# My_STM32_BOARD_FUNCTION_SCH.net
KiCad netlist of a schematic drawn in Altium Designer
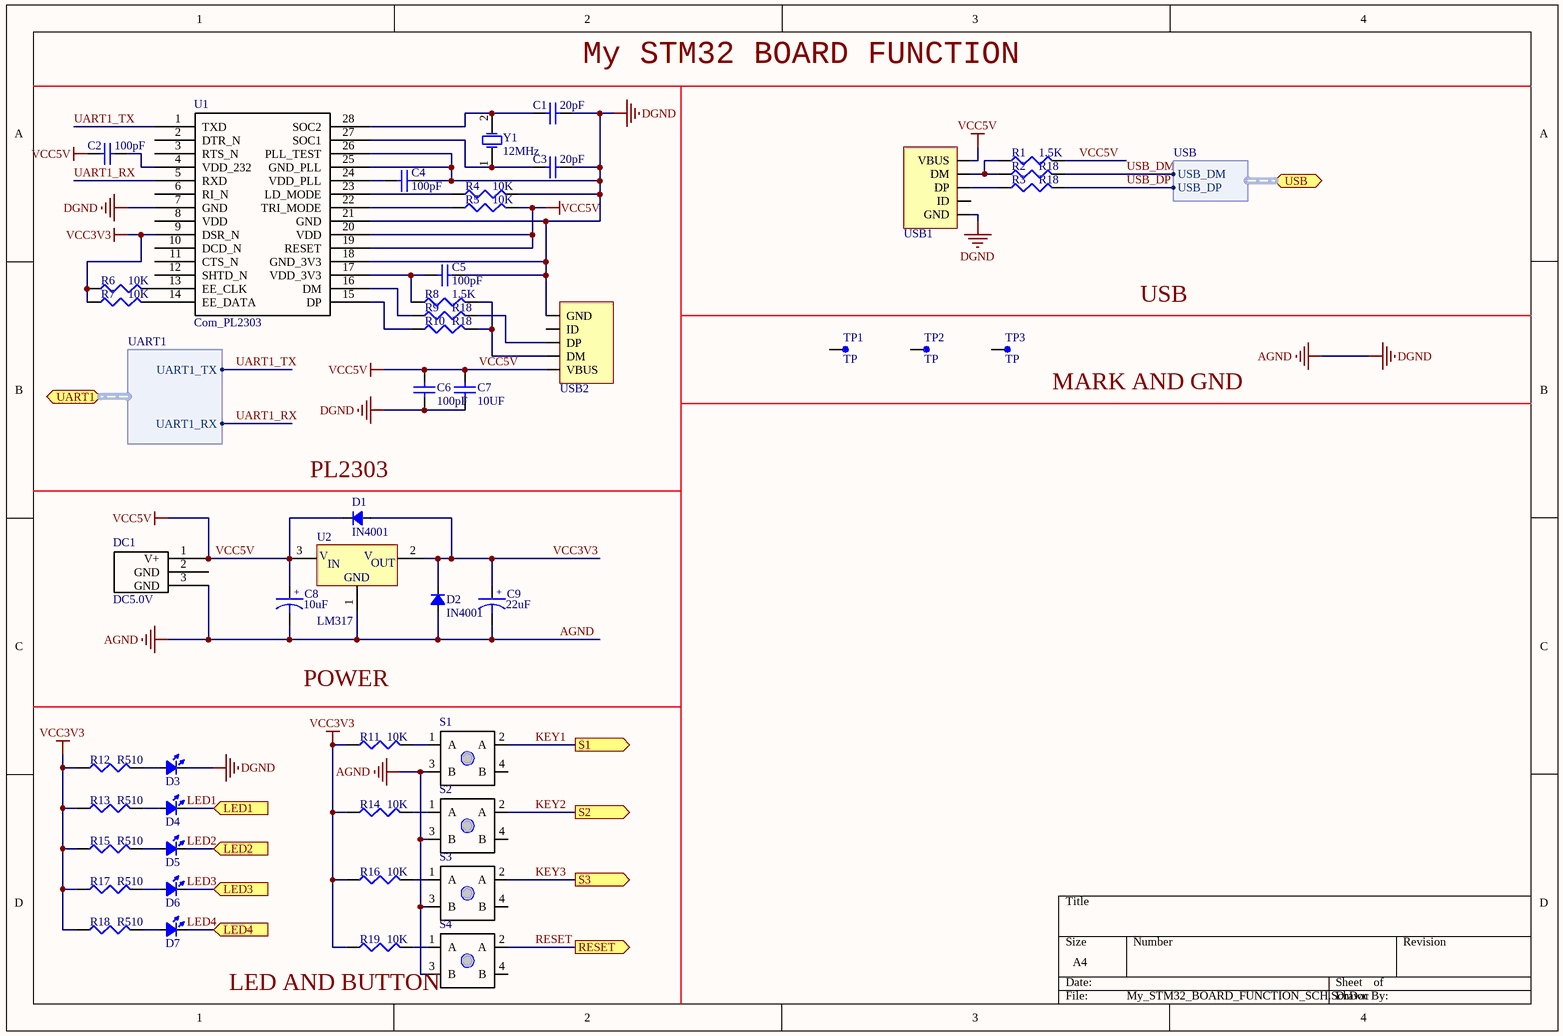
[diagram p0: My_STM32_BOARD_FUNCTION_SCH.SchDoc]

(export (version "E")
  (design (tool "Eeschema 10.0.6"))
  (components
    (comp (ref "C1")
      (value "20pF")
      (footprint "0402")
      (description "Capacitor")
      (fields (field (name "Comment") "Cap") (field (name "PUBLISHER") "Altium Limited"))
      (libsource (lib "Miscellaneous Devices") (part "Cap"))
    )
    (comp (ref "C2")
      (value "100pF")
      (footprint "0402")
      (description "Capacitor")
      (fields (field (name "Comment") "Cap") (field (name "PUBLISHER") "Altium Limited"))
      (libsource (lib "Miscellaneous Devices") (part "Cap"))
    )
    (comp (ref "C3")
      (value "20pF")
      (footprint "0402")
      (description "Capacitor")
      (fields (field (name "Comment") "Cap") (field (name "PUBLISHER") "Altium Limited"))
      (libsource (lib "Miscellaneous Devices") (part "Cap"))
    )
    (comp (ref "C4")
      (value "100pF")
      (footprint "0402")
      (description "Capacitor")
      (fields (field (name "Comment") "Cap") (field (name "PUBLISHER") "Altium Limited"))
      (libsource (lib "Miscellaneous Devices") (part "Cap"))
    )
    (comp (ref "C5")
      (value "100pF")
      (footprint "0402")
      (description "Capacitor")
      (fields (field (name "Comment") "Cap") (field (name "PUBLISHER") "Altium Limited"))
      (libsource (lib "Miscellaneous Devices") (part "Cap"))
    )
    (comp (ref "C6")
      (value "100pF")
      (footprint "0402")
      (description "Capacitor")
      (fields (field (name "Comment") "Cap") (field (name "PUBLISHER") "Altium Limited"))
      (libsource (lib "Miscellaneous Devices") (part "Cap"))
    )
    (comp (ref "C7")
      (value "10UF")
      (footprint "2029")
      (description "Capacitor")
      (fields (field (name "Comment") "Cap") (field (name "PUBLISHER") "Altium Limited"))
      (libsource (lib "Miscellaneous Devices") (part "Cap"))
    )
    (comp (ref "C8")
      (value "Cap_Pol")
      (footprint "Cap_Pol_F5")
      (description "Capacitor")
      (fields (field (name "ALTIUM_UNNAMED_1") "10uF"))
      (libsource (lib "My_Integrated_Library") (part "Cap_Pol"))
    )
    (comp (ref "C9")
      (value "22uF")
      (footprint "Cap_Pol_F6")
      (description "Capacitor")
      (fields (field (name "Comment") "Cap_Pol"))
      (libsource (lib "My_Integrated_Library") (part "Cap_Pol"))
    )
    (comp (ref "D1")
      (value "IN4001")
      (footprint "DIODE_DO-214AC")
      (description "Diode")
      (libsource (lib "My_Integrated_Library") (part "Diode_SMA"))
    )
    (comp (ref "D2")
      (value "IN4001")
      (footprint "DIODE_DO-214AC")
      (description "Diode")
      (libsource (lib "My_Integrated_Library") (part "Diode_SMA"))
    )
    (comp (ref "D3")
      (value "LED_0805")
      (footprint "LED_0805_RED")
      (description "LED")
      (libsource (lib "My_Integrated_Library") (part "LED_0805"))
    )
    (comp (ref "D4")
      (value "LED_0805")
      (footprint "LED_1206_BLUE")
      (description "LED")
      (libsource (lib "My_Integrated_Library") (part "LED_0805"))
    )
    (comp (ref "D5")
      (value "LED_0805")
      (footprint "LED_1206_BLUE")
      (description "LED")
      (libsource (lib "My_Integrated_Library") (part "LED_0805"))
    )
    (comp (ref "D6")
      (value "LED_0805")
      (footprint "LED_1206_BLUE")
      (description "LED")
      (libsource (lib "My_Integrated_Library") (part "LED_0805"))
    )
    (comp (ref "D7")
      (value "LED_0805")
      (footprint "LED_1206_BLUE")
      (description "LED")
      (libsource (lib "My_Integrated_Library") (part "LED_0805"))
    )
    (comp (ref "DC1")
      (value "DC5.0V")
      (footprint "DC_5V")
      (libsource (lib "My_Integrated_Library") (part "DC5V"))
    )
    (comp (ref "R1")
      (value "1.5K")
      (footprint "6-0805_N")
      (description "Resistor")
      (fields (field (name "Comment") "Res3") (field (name "PUBLISHER") "Altium Limited"))
      (libsource (lib "Miscellaneous Devices") (part "Res3"))
    )
    (comp (ref "R2")
      (value "R18")
      (footprint "6-0805_N")
      (description "Resistor")
      (fields (field (name "Comment") "Res3") (field (name "PUBLISHER") "Altium Limited"))
      (libsource (lib "Miscellaneous Devices") (part "Res3"))
    )
    (comp (ref "R3")
      (value "R18")
      (footprint "6-0805_N")
      (description "Resistor")
      (fields (field (name "Comment") "Res3") (field (name "PUBLISHER") "Altium Limited"))
      (libsource (lib "Miscellaneous Devices") (part "Res3"))
    )
    (comp (ref "R4")
      (value "10K")
      (footprint "6-0805_N")
      (description "Resistor")
      (fields (field (name "Comment") "Res3") (field (name "PUBLISHER") "Altium Limited"))
      (libsource (lib "Miscellaneous Devices") (part "Res3"))
    )
    (comp (ref "R5")
      (value "10K")
      (footprint "6-0805_N")
      (description "Resistor")
      (fields (field (name "Comment") "Res3") (field (name "PUBLISHER") "Altium Limited"))
      (libsource (lib "Miscellaneous Devices") (part "Res3"))
    )
    (comp (ref "R6")
      (value "10K")
      (footprint "6-0805_N")
      (description "Resistor")
      (fields (field (name "Comment") "Res3") (field (name "PUBLISHER") "Altium Limited"))
      (libsource (lib "Miscellaneous Devices") (part "Res3"))
    )
    (comp (ref "R7")
      (value "10K")
      (footprint "6-0805_N")
      (description "Resistor")
      (fields (field (name "Comment") "Res3") (field (name "PUBLISHER") "Altium Limited"))
      (libsource (lib "Miscellaneous Devices") (part "Res3"))
    )
    (comp (ref "R8")
      (value "1.5K")
      (footprint "6-0805_N")
      (description "Resistor")
      (fields (field (name "Comment") "Res3") (field (name "PUBLISHER") "Altium Limited"))
      (libsource (lib "Miscellaneous Devices") (part "Res3"))
    )
    (comp (ref "R9")
      (value "R18")
      (footprint "6-0805_N")
      (description "Resistor")
      (fields (field (name "Comment") "Res3") (field (name "PUBLISHER") "Altium Limited"))
      (libsource (lib "Miscellaneous Devices") (part "Res3"))
    )
    (comp (ref "R10")
      (value "R18")
      (footprint "6-0805_N")
      (description "Resistor")
      (fields (field (name "Comment") "Res3") (field (name "PUBLISHER") "Altium Limited"))
      (libsource (lib "Miscellaneous Devices") (part "Res3"))
    )
    (comp (ref "R11")
      (value "10K")
      (footprint "6-0805_N")
      (description "Resistor")
      (fields (field (name "Comment") "Res3") (field (name "PUBLISHER") "Altium Limited"))
      (libsource (lib "Miscellaneous Devices") (part "Res3"))
    )
    (comp (ref "R12")
      (value "R510")
      (footprint "6-0805_N")
      (description "Resistor")
      (fields (field (name "Comment") "Res3") (field (name "PUBLISHER") "Altium Limited"))
      (libsource (lib "Miscellaneous Devices") (part "Res3"))
    )
    (comp (ref "R13")
      (value "R510")
      (footprint "6-0805_N")
      (description "Resistor")
      (fields (field (name "Comment") "Res3") (field (name "PUBLISHER") "Altium Limited"))
      (libsource (lib "Miscellaneous Devices") (part "Res3"))
    )
    (comp (ref "R14")
      (value "10K")
      (footprint "6-0805_N")
      (description "Resistor")
      (fields (field (name "Comment") "Res3") (field (name "PUBLISHER") "Altium Limited"))
      (libsource (lib "Miscellaneous Devices") (part "Res3"))
    )
    (comp (ref "R15")
      (value "R510")
      (footprint "6-0805_N")
      (description "Resistor")
      (fields (field (name "Comment") "Res3") (field (name "PUBLISHER") "Altium Limited"))
      (libsource (lib "Miscellaneous Devices") (part "Res3"))
    )
    (comp (ref "R16")
      (value "10K")
      (footprint "6-0805_N")
      (description "Resistor")
      (fields (field (name "Comment") "Res3") (field (name "PUBLISHER") "Altium Limited"))
      (libsource (lib "Miscellaneous Devices") (part "Res3"))
    )
    (comp (ref "R17")
      (value "R510")
      (footprint "6-0805_N")
      (description "Resistor")
      (fields (field (name "Comment") "Res3") (field (name "PUBLISHER") "Altium Limited"))
      (libsource (lib "Miscellaneous Devices") (part "Res3"))
    )
    (comp (ref "R18")
      (value "R510")
      (footprint "6-0805_N")
      (description "Resistor")
      (fields (field (name "Comment") "Res3") (field (name "PUBLISHER") "Altium Limited"))
      (libsource (lib "Miscellaneous Devices") (part "Res3"))
    )
    (comp (ref "R19")
      (value "10K")
      (footprint "6-0805_N")
      (description "Resistor")
      (fields (field (name "Comment") "Res3") (field (name "PUBLISHER") "Altium Limited"))
      (libsource (lib "Miscellaneous Devices") (part "Res3"))
    )
    (comp (ref "S1")
      (value "Button")
      (footprint "My_Button")
      (description "四脚按键")
      (libsource (lib "My_Integrated_Library") (part "KEY_K4"))
    )
    (comp (ref "S2")
      (value "Button")
      (footprint "My_Button")
      (description "四脚按键")
      (libsource (lib "My_Integrated_Library") (part "KEY_K4"))
    )
    (comp (ref "S3")
      (value "Button")
      (footprint "My_Button")
      (description "四脚按键")
      (libsource (lib "My_Integrated_Library") (part "KEY_K4"))
    )
    (comp (ref "S4")
      (value "Button")
      (footprint "My_Button")
      (description "四脚按键")
      (libsource (lib "My_Integrated_Library") (part "KEY_K4"))
    )
    (comp (ref "TP1") (value "TP") (footprint "MARK") (libsource (lib "My_Integrated_Library") (part "TP")))
    (comp (ref "TP2") (value "TP") (footprint "MARK") (libsource (lib "My_Integrated_Library") (part "TP")))
    (comp (ref "TP3") (value "TP") (footprint "MARK") (libsource (lib "My_Integrated_Library") (part "TP")))
    (comp (ref "U1")
      (value "Com_PL2303")
      (footprint "SSOP-28")
      (description "PL2303")
      (libsource (lib "My_Integrated_Library") (part "Com_PL2303"))
    )
    (comp (ref "U2")
      (value "LM317")
      (footprint "lm1117")
      (description "LM317 电源芯片")
      (libsource (lib "My_Integrated_Library") (part "Power_LM317"))
    )
    (comp (ref "USB1")
      (value "USB_Mini")
      (footprint "USB_MINI-B")
      (description "USB")
      (libsource (lib "My_Integrated_Library") (part "USB_Mini"))
    )
    (comp (ref "USB2")
      (value "USB_Mini")
      (footprint "USB_MINI-B")
      (description "USB")
      (libsource (lib "") (part "USB_Mini_1"))
    )
    (comp (ref "Y1")
      (value "12MHz")
      (footprint "XT_HC49S_D")
      (description "XTAL")
      (libsource (lib "My_Integrated_Library") (part "XTAL"))
    )
  )
  (nets
    (net (code "3") (name "/KEY1") (class "Default")
      (node (ref "S1") (pin "2") (pinfunction "A_2") (pintype "passive"))
    )
    (net (code "4") (name "/KEY2") (class "Default")
      (node (ref "S2") (pin "2") (pinfunction "A_2") (pintype "passive"))
    )
    (net (code "5") (name "/KEY3") (class "Default")
      (node (ref "S3") (pin "2") (pinfunction "A_2") (pintype "passive"))
    )
    (net (code "6") (name "/LED1") (class "Default")
      (node (ref "D4") (pin "2") (pinfunction "K_2") (pintype "passive"))
    )
    (net (code "7") (name "/LED2") (class "Default")
      (node (ref "D5") (pin "2") (pinfunction "K_2") (pintype "passive"))
    )
    (net (code "8") (name "/LED3") (class "Default")
      (node (ref "D6") (pin "2") (pinfunction "K_2") (pintype "passive"))
    )
    (net (code "9") (name "/LED4") (class "Default")
      (node (ref "D7") (pin "2") (pinfunction "K_2") (pintype "passive"))
    )
    (net (code "10") (name "/RESET") (class "Default")
      (node (ref "S4") (pin "2") (pinfunction "A_2") (pintype "passive"))
    )
    (net (code "11") (name "/UART1_RX") (class "Default")
      (node (ref "U1") (pin "5") (pinfunction "RXD_5") (pintype "passive"))
    )
    (net (code "12") (name "/UART1_TX") (class "Default")
      (node (ref "U1") (pin "1") (pinfunction "TXD_1") (pintype "passive"))
    )
    (net (code "13") (name "/USB_DM") (class "Default")
      (node (ref "R2") (pin "2") (pinfunction "2_2") (pintype "passive"))
    )
    (net (code "14") (name "/USB_DP") (class "Default")
      (node (ref "R3") (pin "2") (pinfunction "2_2") (pintype "passive"))
    )
    (net (code "17") (name "AGND") (class "Default")
      (node (ref "C1") (pin "2") (pinfunction "2_2") (pintype "passive"))
      (node (ref "C3") (pin "2") (pinfunction "2_2") (pintype "passive"))
      (node (ref "C4") (pin "2") (pinfunction "2_2") (pintype "passive"))
      (node (ref "C5") (pin "2") (pinfunction "2_2") (pintype "passive"))
      (node (ref "C6") (pin "1") (pinfunction "1_1") (pintype "passive"))
      (node (ref "C7") (pin "1") (pinfunction "1_1") (pintype "passive"))
      (node (ref "C8") (pin "2") (pinfunction "2_2") (pintype "passive"))
      (node (ref "C9") (pin "2") (pinfunction "2_2") (pintype "passive"))
      (node (ref "D2") (pin "1") (pinfunction "A_1") (pintype "passive"))
      (node (ref "D3") (pin "2") (pinfunction "K_2") (pintype "passive"))
      (node (ref "DC1") (pin "3") (pinfunction "GND_3") (pintype "passive"))
      (node (ref "R4") (pin "2") (pinfunction "2_2") (pintype "passive"))
      (node (ref "S1") (pin "3") (pinfunction "B_3") (pintype "passive"))
      (node (ref "S2") (pin "3") (pinfunction "B_3") (pintype "passive"))
      (node (ref "S3") (pin "3") (pinfunction "B_3") (pintype "passive"))
      (node (ref "S4") (pin "3") (pinfunction "B_3") (pintype "passive"))
      (node (ref "U1") (pin "18") (pinfunction "GND_3V3_18") (pintype "passive"))
      (node (ref "U1") (pin "21") (pinfunction "GND_21") (pintype "passive"))
      (node (ref "U1") (pin "25") (pinfunction "GND_PLL_25") (pintype "passive"))
      (node (ref "U1") (pin "26") (pinfunction "PLL_TEST_26") (pintype "passive"))
      (node (ref "U1") (pin "7") (pinfunction "GND_7") (pintype "passive"))
      (node (ref "U2") (pin "1") (pinfunction "GND_1") (pintype "passive"))
      (node (ref "USB1") (pin "5") (pinfunction "GND_5") (pintype "passive"))
      (node (ref "USB2") (pin "5") (pinfunction "GND_5") (pintype "passive"))
    )
    (net (code "18") (name "Net-(D3-A)") (class "Default")
      (node (ref "D3") (pin "1") (pinfunction "A_1") (pintype "passive"))
      (node (ref "R12") (pin "2") (pinfunction "2_2") (pintype "passive"))
    )
    (net (code "19") (name "Net-(D4-A)") (class "Default")
      (node (ref "D4") (pin "1") (pinfunction "A_1") (pintype "passive"))
      (node (ref "R13") (pin "2") (pinfunction "2_2") (pintype "passive"))
    )
    (net (code "20") (name "Net-(D5-A)") (class "Default")
      (node (ref "D5") (pin "1") (pinfunction "A_1") (pintype "passive"))
      (node (ref "R15") (pin "2") (pinfunction "2_2") (pintype "passive"))
    )
    (net (code "21") (name "Net-(D6-A)") (class "Default")
      (node (ref "D6") (pin "1") (pinfunction "A_1") (pintype "passive"))
      (node (ref "R17") (pin "2") (pinfunction "2_2") (pintype "passive"))
    )
    (net (code "22") (name "Net-(D7-A)") (class "Default")
      (node (ref "D7") (pin "1") (pinfunction "A_1") (pintype "passive"))
      (node (ref "R18") (pin "2") (pinfunction "2_2") (pintype "passive"))
    )
    (net (code "23") (name "Net-(R11-Pad2)") (class "Default")
      (node (ref "R11") (pin "2") (pinfunction "2_2") (pintype "passive"))
      (node (ref "S1") (pin "1") (pinfunction "A_1") (pintype "passive"))
    )
    (net (code "24") (name "Net-(R14-Pad2)") (class "Default")
      (node (ref "R14") (pin "2") (pinfunction "2_2") (pintype "passive"))
      (node (ref "S2") (pin "1") (pinfunction "A_1") (pintype "passive"))
    )
    (net (code "25") (name "Net-(R16-Pad2)") (class "Default")
      (node (ref "R16") (pin "2") (pinfunction "2_2") (pintype "passive"))
      (node (ref "S3") (pin "1") (pinfunction "A_1") (pintype "passive"))
    )
    (net (code "26") (name "Net-(R19-Pad2)") (class "Default")
      (node (ref "R19") (pin "2") (pinfunction "2_2") (pintype "passive"))
      (node (ref "S4") (pin "1") (pinfunction "A_1") (pintype "passive"))
    )
    (net (code "27") (name "Net-(U1-DM)") (class "Default")
      (node (ref "R9") (pin "1") (pinfunction "1_1") (pintype "passive"))
      (node (ref "U1") (pin "16") (pinfunction "DM_16") (pintype "passive"))
    )
    (net (code "28") (name "Net-(U1-DP)") (class "Default")
      (node (ref "R10") (pin "1") (pinfunction "1_1") (pintype "passive"))
      (node (ref "U1") (pin "15") (pinfunction "DP_15") (pintype "passive"))
    )
    (net (code "29") (name "Net-(U1-EE_CLK)") (class "Default")
      (node (ref "R6") (pin "2") (pinfunction "2_2") (pintype "passive"))
      (node (ref "U1") (pin "13") (pinfunction "EE_CLK_13") (pintype "passive"))
    )
    (net (code "30") (name "Net-(U1-EE_DATA)") (class "Default")
      (node (ref "R7") (pin "2") (pinfunction "2_2") (pintype "passive"))
      (node (ref "U1") (pin "14") (pinfunction "EE_DATA_14") (pintype "passive"))
    )
    (net (code "31") (name "Net-(U1-LD_MODE)") (class "Default")
      (node (ref "R4") (pin "1") (pinfunction "1_1") (pintype "passive"))
      (node (ref "U1") (pin "23") (pinfunction "LD_MODE_23") (pintype "passive"))
    )
    (net (code "32") (name "Net-(U1-SOC1)") (class "Default")
      (node (ref "C3") (pin "1") (pinfunction "1_1") (pintype "passive"))
      (node (ref "U1") (pin "27") (pinfunction "SOC1_27") (pintype "passive"))
      (node (ref "Y1") (pin "1") (pinfunction "1_1") (pintype "passive"))
    )
    (net (code "33") (name "Net-(U1-SOC2)") (class "Default")
      (node (ref "C1") (pin "1") (pinfunction "1_1") (pintype "passive"))
      (node (ref "U1") (pin "28") (pinfunction "SOC2_28") (pintype "passive"))
      (node (ref "Y1") (pin "2") (pinfunction "2_2") (pintype "passive"))
    )
    (net (code "34") (name "Net-(U1-TRI_MODE)") (class "Default")
      (node (ref "R5") (pin "1") (pinfunction "1_1") (pintype "passive"))
      (node (ref "U1") (pin "22") (pinfunction "TRI_MODE_22") (pintype "passive"))
    )
    (net (code "35") (name "Net-(U1-VDD_3V3)") (class "Default")
      (node (ref "C5") (pin "1") (pinfunction "1_1") (pintype "passive"))
      (node (ref "R8") (pin "1") (pinfunction "1_1") (pintype "passive"))
      (node (ref "U1") (pin "17") (pinfunction "VDD_3V3_17") (pintype "passive"))
    )
    (net (code "36") (name "Net-(U1-VDD_232)") (class "Default")
      (node (ref "C2") (pin "1") (pinfunction "1_1") (pintype "passive"))
      (node (ref "U1") (pin "4") (pinfunction "VDD_232_4") (pintype "passive"))
    )
    (net (code "37") (name "Net-(U1-VDD_PLL)") (class "Default")
      (node (ref "C4") (pin "1") (pinfunction "1_1") (pintype "passive"))
      (node (ref "U1") (pin "24") (pinfunction "VDD_PLL_24") (pintype "passive"))
    )
    (net (code "38") (name "Net-(USB1-DM)") (class "Default")
      (node (ref "R1") (pin "1") (pinfunction "1_1") (pintype "passive"))
      (node (ref "R2") (pin "1") (pinfunction "1_1") (pintype "passive"))
      (node (ref "USB1") (pin "2") (pinfunction "DM_2") (pintype "passive"))
    )
    (net (code "39") (name "Net-(USB1-DP)") (class "Default")
      (node (ref "R3") (pin "1") (pinfunction "1_1") (pintype "passive"))
      (node (ref "USB1") (pin "3") (pinfunction "DP_3") (pintype "passive"))
    )
    (net (code "40") (name "Net-(USB2-DM)") (class "Default")
      (node (ref "R10") (pin "2") (pinfunction "2_2") (pintype "passive"))
      (node (ref "R8") (pin "2") (pinfunction "2_2") (pintype "passive"))
      (node (ref "USB2") (pin "2") (pinfunction "DM_2") (pintype "passive"))
    )
    (net (code "41") (name "Net-(USB2-DP)") (class "Default")
      (node (ref "R9") (pin "2") (pinfunction "2_2") (pintype "passive"))
      (node (ref "USB2") (pin "3") (pinfunction "DP_3") (pintype "passive"))
    )
    (net (code "42") (name "VCC3V3") (class "Default")
      (node (ref "C9") (pin "1") (pinfunction "1_1") (pintype "passive"))
      (node (ref "D1") (pin "1") (pinfunction "A_1") (pintype "passive"))
      (node (ref "D2") (pin "2") (pinfunction "K_2") (pintype "passive"))
      (node (ref "R11") (pin "1") (pinfunction "1_1") (pintype "passive"))
      (node (ref "R12") (pin "1") (pinfunction "1_1") (pintype "passive"))
      (node (ref "R13") (pin "1") (pinfunction "1_1") (pintype "passive"))
      (node (ref "R14") (pin "1") (pinfunction "1_1") (pintype "passive"))
      (node (ref "R15") (pin "1") (pinfunction "1_1") (pintype "passive"))
      (node (ref "R16") (pin "1") (pinfunction "1_1") (pintype "passive"))
      (node (ref "R17") (pin "1") (pinfunction "1_1") (pintype "passive"))
      (node (ref "R18") (pin "1") (pinfunction "1_1") (pintype "passive"))
      (node (ref "R19") (pin "1") (pinfunction "1_1") (pintype "passive"))
      (node (ref "R6") (pin "1") (pinfunction "1_1") (pintype "passive"))
      (node (ref "R7") (pin "1") (pinfunction "1_1") (pintype "passive"))
      (node (ref "U1") (pin "9") (pinfunction "DSR_N_9") (pintype "passive"))
      (node (ref "U2") (pin "2") (pinfunction "VOUT_2") (pintype "passive"))
    )
    (net (code "43") (name "VCC5V") (class "Default")
      (node (ref "C2") (pin "2") (pinfunction "2_2") (pintype "passive"))
      (node (ref "C6") (pin "2") (pinfunction "2_2") (pintype "passive"))
      (node (ref "C7") (pin "2") (pinfunction "2_2") (pintype "passive"))
      (node (ref "C8") (pin "1") (pinfunction "1_1") (pintype "passive"))
      (node (ref "D1") (pin "2") (pinfunction "K_2") (pintype "passive"))
      (node (ref "DC1") (pin "1") (pinfunction "V+_1") (pintype "passive"))
      (node (ref "R1") (pin "2") (pinfunction "2_2") (pintype "passive"))
      (node (ref "R5") (pin "2") (pinfunction "2_2") (pintype "passive"))
      (node (ref "U1") (pin "19") (pinfunction "RESET_19") (pintype "passive"))
      (node (ref "U1") (pin "20") (pinfunction "VDD_20") (pintype "passive"))
      (node (ref "U2") (pin "3") (pinfunction "VIN_3") (pintype "passive"))
      (node (ref "USB1") (pin "1") (pinfunction "VBUS_1") (pintype "passive"))
      (node (ref "USB2") (pin "1") (pinfunction "VBUS_1") (pintype "passive"))
    )
    (net (code "44") (name "unconnected-(DC1-GND-Pad2)") (class "Default")
      (node (ref "DC1") (pin "2") (pinfunction "GND_2") (pintype "passive"))
    )
    (net (code "45") (name "unconnected-(S1-B-Pad4)") (class "Default")
      (node (ref "S1") (pin "4") (pinfunction "B_4") (pintype "passive"))
    )
    (net (code "46") (name "unconnected-(S2-B-Pad4)") (class "Default")
      (node (ref "S2") (pin "4") (pinfunction "B_4") (pintype "passive"))
    )
    (net (code "47") (name "unconnected-(S3-B-Pad4)") (class "Default")
      (node (ref "S3") (pin "4") (pinfunction "B_4") (pintype "passive"))
    )
    (net (code "48") (name "unconnected-(S4-B-Pad4)") (class "Default")
      (node (ref "S4") (pin "4") (pinfunction "B_4") (pintype "passive"))
    )
    (net (code "49") (name "unconnected-(TP1-Pad1)") (class "Default")
      (node (ref "TP1") (pin "1") (pinfunction "1_1") (pintype "passive"))
    )
    (net (code "50") (name "unconnected-(TP2-Pad1)") (class "Default")
      (node (ref "TP2") (pin "1") (pinfunction "1_1") (pintype "passive"))
    )
    (net (code "51") (name "unconnected-(TP3-Pad1)") (class "Default")
      (node (ref "TP3") (pin "1") (pinfunction "1_1") (pintype "passive"))
    )
    (net (code "52") (name "unconnected-(U1-CTS_N-Pad11)") (class "Default")
      (node (ref "U1") (pin "11") (pinfunction "CTS_N_11") (pintype "passive"))
    )
    (net (code "53") (name "unconnected-(U1-DCD_N-Pad10)") (class "Default")
      (node (ref "U1") (pin "10") (pinfunction "DCD_N_10") (pintype "passive"))
    )
    (net (code "54") (name "unconnected-(U1-DTR_N-Pad2)") (class "Default")
      (node (ref "U1") (pin "2") (pinfunction "DTR_N_2") (pintype "passive"))
    )
    (net (code "55") (name "unconnected-(U1-RI_N-Pad6)") (class "Default")
      (node (ref "U1") (pin "6") (pinfunction "RI_N_6") (pintype "passive"))
    )
    (net (code "56") (name "unconnected-(U1-RTS_N-Pad3)") (class "Default")
      (node (ref "U1") (pin "3") (pinfunction "RTS_N_3") (pintype "passive"))
    )
    (net (code "57") (name "unconnected-(U1-SHTD_N-Pad12)") (class "Default")
      (node (ref "U1") (pin "12") (pinfunction "SHTD_N_12") (pintype "passive"))
    )
    (net (code "58") (name "unconnected-(U1-VDD-Pad8)") (class "Default")
      (node (ref "U1") (pin "8") (pinfunction "VDD_8") (pintype "passive"))
    )
    (net (code "59") (name "unconnected-(USB1-ID-Pad4)") (class "Default")
      (node (ref "USB1") (pin "4") (pinfunction "ID_4") (pintype "passive"))
    )
    (net (code "60") (name "unconnected-(USB2-ID-Pad4)") (class "Default")
      (node (ref "USB2") (pin "4") (pinfunction "ID_4") (pintype "passive"))
    )
  )
)
